# PP2_ptB.net
KiCad netlist of a schematic drawn in Altium Designer
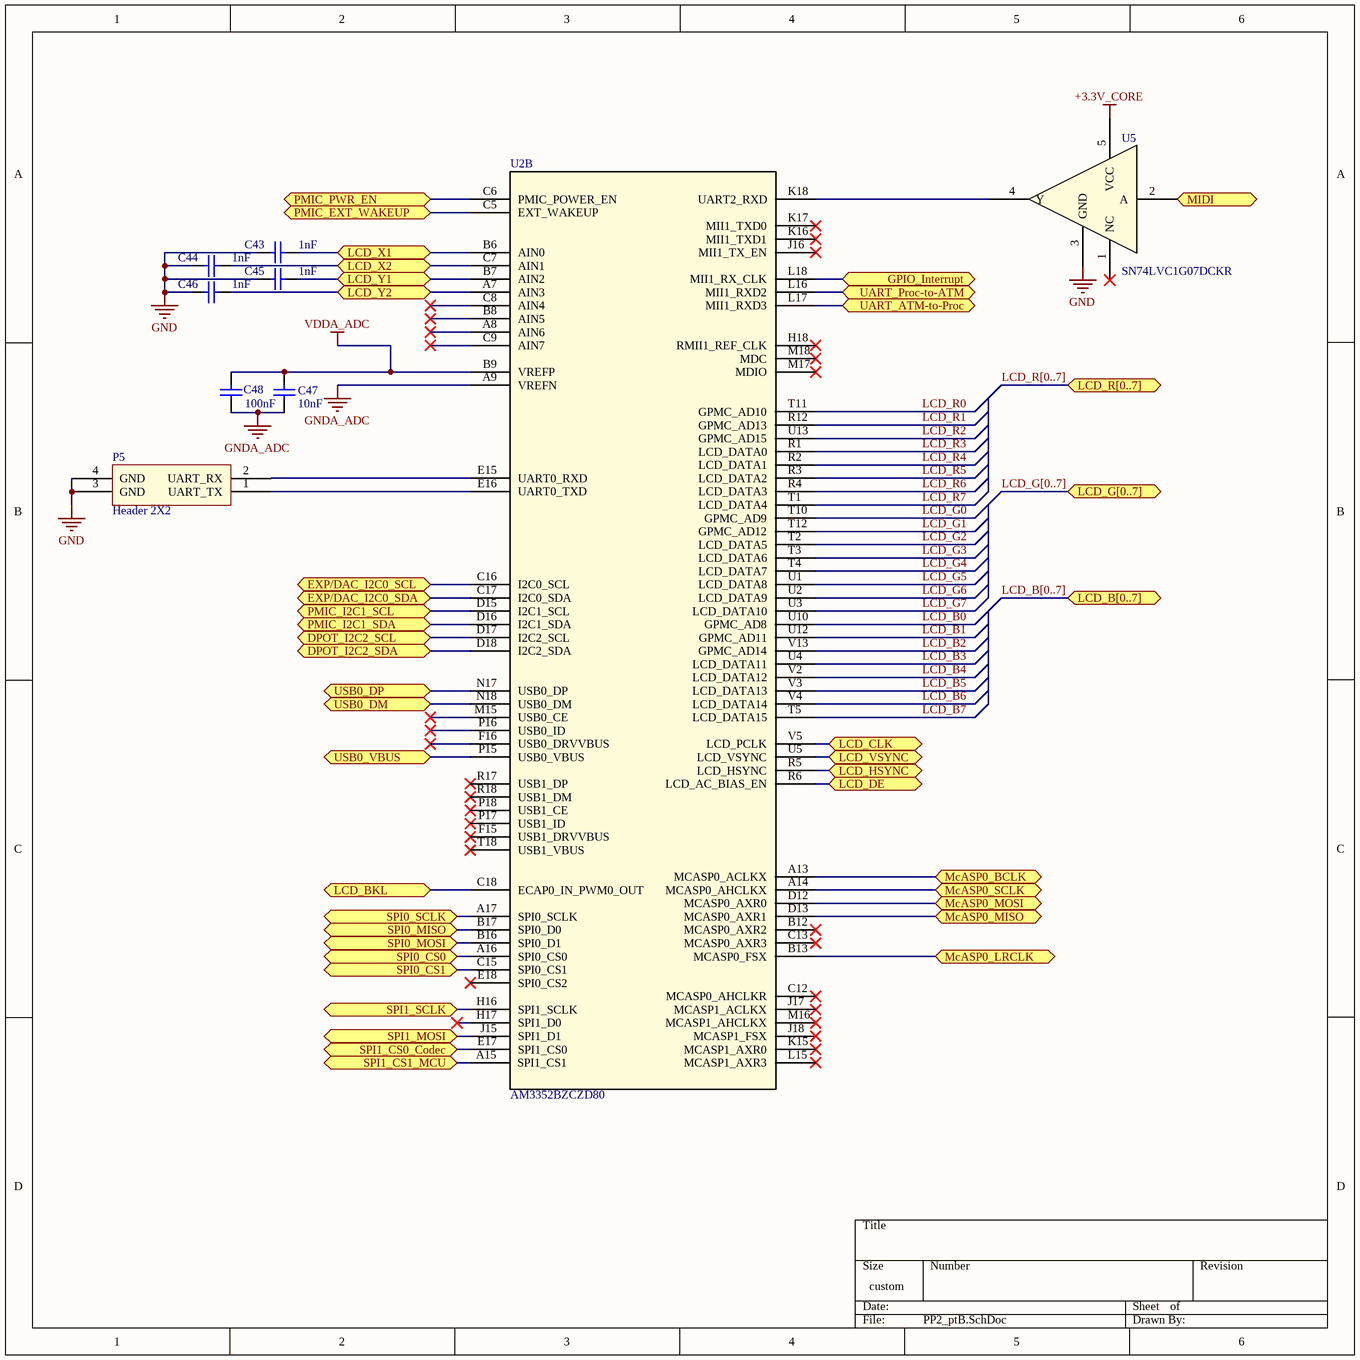
[diagram p0: PP2_ptB.SchDoc]

(export (version "E")
  (design (tool "Eeschema 10.0.6"))
  (components
    (comp (ref "C43")
      (value "1nF")
      (footprint "CAPC1608X08")
      (description "Capacitor")
      (fields (field (name "Comment") "Cap 1nF"))
      (libsource (lib "Michel") (part "Cap"))
    )
    (comp (ref "C44")
      (value "1nF")
      (footprint "CAPC1608X08")
      (description "Capacitor")
      (fields (field (name "Comment") "Cap 1nF"))
      (libsource (lib "Michel") (part "Cap"))
    )
    (comp (ref "C45")
      (value "1nF")
      (footprint "CAPC1608X08")
      (description "Capacitor")
      (fields (field (name "Comment") "Cap 1nF"))
      (libsource (lib "Michel") (part "Cap"))
    )
    (comp (ref "C46")
      (value "1nF")
      (footprint "CAPC1608X08")
      (description "Capacitor")
      (fields (field (name "Comment") "Cap 1nF"))
      (libsource (lib "Michel") (part "Cap"))
    )
    (comp (ref "C47")
      (value "10nF")
      (footprint "CAPC1005X05 (0402)")
      (description "Capacitor")
      (fields (field (name "Comment") "Cap 10uF"))
      (libsource (lib "Michel") (part "Cap"))
    )
    (comp (ref "C48")
      (value "100nF")
      (footprint "CAPC1005X05 (0402)")
      (description "Capacitor")
      (fields (field (name "Comment") "Cap 100nF"))
      (libsource (lib "Michel") (part "Cap"))
    )
    (comp (ref "P5")
      (value "Header 2X2")
      (footprint "CONN_1241050-2_T")
      (description "Header, 2-Pin, Dual row")
      (libsource (lib "Michel") (part "UART"))
    )
    (comp (ref "U2")
      (value "AM3352BZCZD80")
      (footprint "ZCZ324")
      (description "Microprocesseur ARM")
      (libsource (lib "Michel") (part "AM3352BZCZD80"))
    )
    (comp (ref "U5")
      (value "SN74LVC1G07DCKR")
      (footprint "DCK5")
      (description "Buffers & Transmetteurs")
      (libsource (lib "Michel") (part "SN74LVC1G07DCKR"))
    )
  )
  (nets
    (net (code "1") (name "+3.3V_CORE") (class "Default")
      (node (ref "U5") (pin "5") (pinfunction "VCC_5") (pintype "power_in"))
    )
    (net (code "2") (name "/DPOT_I2C2_SCL") (class "Default")
      (node (ref "U2") (pin "D17") (pinfunction "I2C2_SCL_D17") (pintype "passive"))
    )
    (net (code "3") (name "/DPOT_I2C2_SDA") (class "Default")
      (node (ref "U2") (pin "D18") (pinfunction "I2C2_SDA_D18") (pintype "passive"))
    )
    (net (code "4") (name "/EXP{slash}DAC_I2C0_SCL") (class "Default")
      (node (ref "U2") (pin "C16") (pinfunction "I2C0_SCL_C16") (pintype "passive"))
    )
    (net (code "5") (name "/EXP{slash}DAC_I2C0_SDA") (class "Default")
      (node (ref "U2") (pin "C17") (pinfunction "I2C0_SDA_C17") (pintype "passive"))
    )
    (net (code "6") (name "/GPIO_Interrupt") (class "Default")
      (node (ref "U2") (pin "L18") (pinfunction "MII1_RX_CLK_L18") (pintype "passive"))
    )
    (net (code "7") (name "/LCD_B0") (class "Default")
      (node (ref "U2") (pin "U10") (pinfunction "GPMC_AD8_U10") (pintype "passive"))
    )
    (net (code "8") (name "/LCD_B1") (class "Default")
      (node (ref "U2") (pin "U12") (pinfunction "GPMC_AD11_U12") (pintype "passive"))
    )
    (net (code "9") (name "/LCD_B2") (class "Default")
      (node (ref "U2") (pin "V13") (pinfunction "GPMC_AD14_V13") (pintype "passive"))
    )
    (net (code "10") (name "/LCD_B3") (class "Default")
      (node (ref "U2") (pin "U4") (pinfunction "LCD_DATA11_U4") (pintype "passive"))
    )
    (net (code "11") (name "/LCD_B4") (class "Default")
      (node (ref "U2") (pin "V2") (pinfunction "LCD_DATA12_V2") (pintype "passive"))
    )
    (net (code "12") (name "/LCD_B5") (class "Default")
      (node (ref "U2") (pin "V3") (pinfunction "LCD_DATA13_V3") (pintype "passive"))
    )
    (net (code "13") (name "/LCD_B6") (class "Default")
      (node (ref "U2") (pin "V4") (pinfunction "LCD_DATA14_V4") (pintype "passive"))
    )
    (net (code "14") (name "/LCD_B7") (class "Default")
      (node (ref "U2") (pin "T5") (pinfunction "LCD_DATA15_T5") (pintype "passive"))
    )
    (net (code "15") (name "/LCD_BKL") (class "Default")
      (node (ref "U2") (pin "C18") (pinfunction "ECAP0_IN_PWM0_OUT_C18") (pintype "passive"))
    )
    (net (code "17") (name "/LCD_CLK") (class "Default")
      (node (ref "U2") (pin "V5") (pinfunction "LCD_PCLK_V5") (pintype "passive"))
    )
    (net (code "18") (name "/LCD_DE") (class "Default")
      (node (ref "U2") (pin "R6") (pinfunction "LCD_AC_BIAS_EN_R6") (pintype "passive"))
    )
    (net (code "19") (name "/LCD_G0") (class "Default")
      (node (ref "U2") (pin "T10") (pinfunction "GPMC_AD9_T10") (pintype "passive"))
    )
    (net (code "20") (name "/LCD_G1") (class "Default")
      (node (ref "U2") (pin "T12") (pinfunction "GPMC_AD12_T12") (pintype "passive"))
    )
    (net (code "21") (name "/LCD_G2") (class "Default")
      (node (ref "U2") (pin "T2") (pinfunction "LCD_DATA5_T2") (pintype "passive"))
    )
    (net (code "22") (name "/LCD_G3") (class "Default")
      (node (ref "U2") (pin "T3") (pinfunction "LCD_DATA6_T3") (pintype "passive"))
    )
    (net (code "23") (name "/LCD_G4") (class "Default")
      (node (ref "U2") (pin "T4") (pinfunction "LCD_DATA7_T4") (pintype "passive"))
    )
    (net (code "24") (name "/LCD_G5") (class "Default")
      (node (ref "U2") (pin "U1") (pinfunction "LCD_DATA8_U1") (pintype "passive"))
    )
    (net (code "25") (name "/LCD_G6") (class "Default")
      (node (ref "U2") (pin "U2") (pinfunction "LCD_DATA9_U2") (pintype "passive"))
    )
    (net (code "26") (name "/LCD_G7") (class "Default")
      (node (ref "U2") (pin "U3") (pinfunction "LCD_DATA10_U3") (pintype "passive"))
    )
    (net (code "28") (name "/LCD_HSYNC") (class "Default")
      (node (ref "U2") (pin "R5") (pinfunction "LCD_HSYNC_R5") (pintype "passive"))
    )
    (net (code "29") (name "/LCD_R0") (class "Default")
      (node (ref "U2") (pin "T11") (pinfunction "GPMC_AD10_T11") (pintype "passive"))
    )
    (net (code "30") (name "/LCD_R1") (class "Default")
      (node (ref "U2") (pin "R12") (pinfunction "GPMC_AD13_R12") (pintype "passive"))
    )
    (net (code "31") (name "/LCD_R2") (class "Default")
      (node (ref "U2") (pin "U13") (pinfunction "GPMC_AD15_U13") (pintype "passive"))
    )
    (net (code "32") (name "/LCD_R3") (class "Default")
      (node (ref "U2") (pin "R1") (pinfunction "LCD_DATA0_R1") (pintype "passive"))
    )
    (net (code "33") (name "/LCD_R4") (class "Default")
      (node (ref "U2") (pin "R2") (pinfunction "LCD_DATA1_R2") (pintype "passive"))
    )
    (net (code "34") (name "/LCD_R5") (class "Default")
      (node (ref "U2") (pin "R3") (pinfunction "LCD_DATA2_R3") (pintype "passive"))
    )
    (net (code "35") (name "/LCD_R6") (class "Default")
      (node (ref "U2") (pin "R4") (pinfunction "LCD_DATA3_R4") (pintype "passive"))
    )
    (net (code "36") (name "/LCD_R7") (class "Default")
      (node (ref "U2") (pin "T1") (pinfunction "LCD_DATA4_T1") (pintype "passive"))
    )
    (net (code "38") (name "/LCD_VSYNC") (class "Default")
      (node (ref "U2") (pin "U5") (pinfunction "LCD_VSYNC_U5") (pintype "passive"))
    )
    (net (code "39") (name "/LCD_X1") (class "Default")
      (node (ref "C43") (pin "2") (pinfunction "2_2") (pintype "passive"))
      (node (ref "U2") (pin "B6") (pinfunction "AIN0_B6") (pintype "passive"))
    )
    (net (code "40") (name "/LCD_X2") (class "Default")
      (node (ref "C44") (pin "2") (pinfunction "2_2") (pintype "passive"))
      (node (ref "U2") (pin "C7") (pinfunction "AIN1_C7") (pintype "passive"))
    )
    (net (code "41") (name "/LCD_Y1") (class "Default")
      (node (ref "C45") (pin "2") (pinfunction "2_2") (pintype "passive"))
      (node (ref "U2") (pin "B7") (pinfunction "AIN2_B7") (pintype "passive"))
    )
    (net (code "42") (name "/LCD_Y2") (class "Default")
      (node (ref "C46") (pin "2") (pinfunction "2_2") (pintype "passive"))
      (node (ref "U2") (pin "A7") (pinfunction "AIN3_A7") (pintype "passive"))
    )
    (net (code "43") (name "/MIDI") (class "Default")
      (node (ref "U5") (pin "2") (pinfunction "A_2") (pintype "passive"))
    )
    (net (code "44") (name "/McASP0_BCLK") (class "Default")
      (node (ref "U2") (pin "A13") (pinfunction "MCASP0_ACLKX_A13") (pintype "passive"))
    )
    (net (code "45") (name "/McASP0_LRCLK") (class "Default")
      (node (ref "U2") (pin "B13") (pinfunction "MCASP0_FSX_B13") (pintype "passive"))
    )
    (net (code "46") (name "/McASP0_MISO") (class "Default")
      (node (ref "U2") (pin "D13") (pinfunction "MCASP0_AXR1_D13") (pintype "passive"))
    )
    (net (code "47") (name "/McASP0_MOSI") (class "Default")
      (node (ref "U2") (pin "D12") (pinfunction "MCASP0_AXR0_D12") (pintype "passive"))
    )
    (net (code "48") (name "/McASP0_SCLK") (class "Default")
      (node (ref "U2") (pin "A14") (pinfunction "MCASP0_AHCLKX_A14") (pintype "passive"))
    )
    (net (code "49") (name "/PMIC_EXT_WAKEUP") (class "Default")
      (node (ref "U2") (pin "C5") (pinfunction "EXT_WAKEUP_C5") (pintype "passive"))
    )
    (net (code "50") (name "/PMIC_I2C1_SCL") (class "Default")
      (node (ref "U2") (pin "D15") (pinfunction "I2C1_SCL_D15") (pintype "passive"))
    )
    (net (code "51") (name "/PMIC_I2C1_SDA") (class "Default")
      (node (ref "U2") (pin "D16") (pinfunction "I2C1_SDA_D16") (pintype "passive"))
    )
    (net (code "52") (name "/PMIC_PWR_EN") (class "Default")
      (node (ref "U2") (pin "C6") (pinfunction "PMIC_POWER_EN_C6") (pintype "passive"))
    )
    (net (code "53") (name "/SPI0_CS0") (class "Default")
      (node (ref "U2") (pin "A16") (pinfunction "SPI0_CS0_A16") (pintype "passive"))
    )
    (net (code "54") (name "/SPI0_CS1") (class "Default")
      (node (ref "U2") (pin "C15") (pinfunction "SPI0_CS1_C15") (pintype "passive"))
    )
    (net (code "55") (name "/SPI0_MISO") (class "Default")
      (node (ref "U2") (pin "B17") (pinfunction "SPI0_D0_B17") (pintype "passive"))
    )
    (net (code "56") (name "/SPI0_MOSI") (class "Default")
      (node (ref "U2") (pin "B16") (pinfunction "SPI0_D1_B16") (pintype "passive"))
    )
    (net (code "57") (name "/SPI0_SCLK") (class "Default")
      (node (ref "U2") (pin "A17") (pinfunction "SPI0_SCLK_A17") (pintype "passive"))
    )
    (net (code "58") (name "/SPI1_CS0_Codec") (class "Default")
      (node (ref "U2") (pin "E17") (pinfunction "SPI1_CS0_E17") (pintype "passive"))
    )
    (net (code "59") (name "/SPI1_CS1_MCU") (class "Default")
      (node (ref "U2") (pin "A15") (pinfunction "SPI1_CS1_A15") (pintype "passive"))
    )
    (net (code "60") (name "/SPI1_MOSI") (class "Default")
      (node (ref "U2") (pin "J15") (pinfunction "SPI1_D1_J15") (pintype "passive"))
    )
    (net (code "61") (name "/SPI1_SCLK") (class "Default")
      (node (ref "U2") (pin "H16") (pinfunction "SPI1_SCLK_H16") (pintype "passive"))
    )
    (net (code "62") (name "/UART_ATM-to-Proc") (class "Default")
      (node (ref "U2") (pin "L17") (pinfunction "MII1_RXD3_L17") (pintype "passive"))
    )
    (net (code "63") (name "/UART_Proc-to-ATM") (class "Default")
      (node (ref "U2") (pin "L16") (pinfunction "MII1_RXD2_L16") (pintype "passive"))
    )
    (net (code "64") (name "/USB0_DM") (class "Default")
      (node (ref "U2") (pin "N18") (pinfunction "USB0_DM_N18") (pintype "passive"))
    )
    (net (code "65") (name "/USB0_DP") (class "Default")
      (node (ref "U2") (pin "N17") (pinfunction "USB0_DP_N17") (pintype "passive"))
    )
    (net (code "66") (name "/USB0_VBUS") (class "Default")
      (node (ref "U2") (pin "P15") (pinfunction "USB0_VBUS_P15") (pintype "passive"))
    )
    (net (code "67") (name "GND") (class "Default")
      (node (ref "C43") (pin "1") (pinfunction "1_1") (pintype "passive"))
      (node (ref "C44") (pin "1") (pinfunction "1_1") (pintype "passive"))
      (node (ref "C45") (pin "1") (pinfunction "1_1") (pintype "passive"))
      (node (ref "C46") (pin "1") (pinfunction "1_1") (pintype "passive"))
      (node (ref "P5") (pin "3") (pinfunction "GND_3") (pintype "passive"))
      (node (ref "P5") (pin "4") (pinfunction "GND_4") (pintype "passive"))
      (node (ref "U5") (pin "3") (pinfunction "GND_3") (pintype "power_in"))
    )
    (net (code "68") (name "GNDA_ADC") (class "Default")
      (node (ref "C47") (pin "2") (pinfunction "2_2") (pintype "passive"))
      (node (ref "C48") (pin "2") (pinfunction "2_2") (pintype "passive"))
      (node (ref "U2") (pin "A9") (pinfunction "VREFN_A9") (pintype "passive"))
    )
    (net (code "69") (name "Net-(P5-UART_RX)") (class "Default")
      (node (ref "P5") (pin "2") (pinfunction "UART_RX_2") (pintype "passive"))
      (node (ref "U2") (pin "E15") (pinfunction "UART0_RXD_E15") (pintype "passive"))
    )
    (net (code "70") (name "Net-(P5-UART_TX)") (class "Default")
      (node (ref "P5") (pin "1") (pinfunction "UART_TX_1") (pintype "passive"))
      (node (ref "U2") (pin "E16") (pinfunction "UART0_TXD_E16") (pintype "passive"))
    )
    (net (code "71") (name "Net-(U2B-UART2_RXD)") (class "Default")
      (node (ref "U2") (pin "K18") (pinfunction "UART2_RXD_K18") (pintype "passive"))
      (node (ref "U5") (pin "4") (pinfunction "Y_4") (pintype "passive"))
    )
    (net (code "72") (name "VDDA_ADC") (class "Default")
      (node (ref "C47") (pin "1") (pinfunction "1_1") (pintype "passive"))
      (node (ref "C48") (pin "1") (pinfunction "1_1") (pintype "passive"))
      (node (ref "U2") (pin "B9") (pinfunction "VREFP_B9") (pintype "passive"))
    )
    (net (code "73") (name "unconnected-(U2B-AIN4-PadC8)") (class "Default")
      (node (ref "U2") (pin "C8") (pinfunction "AIN4_C8") (pintype "passive+no_connect"))
    )
    (net (code "74") (name "unconnected-(U2B-AIN5-PadB8)") (class "Default")
      (node (ref "U2") (pin "B8") (pinfunction "AIN5_B8") (pintype "passive+no_connect"))
    )
    (net (code "75") (name "unconnected-(U2B-AIN6-PadA8)") (class "Default")
      (node (ref "U2") (pin "A8") (pinfunction "AIN6_A8") (pintype "passive+no_connect"))
    )
    (net (code "76") (name "unconnected-(U2B-AIN7-PadC9)") (class "Default")
      (node (ref "U2") (pin "C9") (pinfunction "AIN7_C9") (pintype "passive+no_connect"))
    )
    (net (code "77") (name "unconnected-(U2B-MCASP0_AHCLKR-PadC12)") (class "Default")
      (node (ref "U2") (pin "C12") (pinfunction "MCASP0_AHCLKR_C12") (pintype "passive+no_connect"))
    )
    (net (code "78") (name "unconnected-(U2B-MCASP0_AXR2-PadB12)") (class "Default")
      (node (ref "U2") (pin "B12") (pinfunction "MCASP0_AXR2_B12") (pintype "passive+no_connect"))
    )
    (net (code "79") (name "unconnected-(U2B-MCASP0_AXR3-PadC13)") (class "Default")
      (node (ref "U2") (pin "C13") (pinfunction "MCASP0_AXR3_C13") (pintype "passive+no_connect"))
    )
    (net (code "80") (name "unconnected-(U2B-MCASP1_ACLKX-PadJ17)") (class "Default")
      (node (ref "U2") (pin "J17") (pinfunction "MCASP1_ACLKX_J17") (pintype "passive+no_connect"))
    )
    (net (code "81") (name "unconnected-(U2B-MCASP1_AHCLKX-PadM16)") (class "Default")
      (node (ref "U2") (pin "M16") (pinfunction "MCASP1_AHCLKX_M16") (pintype "passive+no_connect"))
    )
    (net (code "82") (name "unconnected-(U2B-MCASP1_AXR0-PadK15)") (class "Default")
      (node (ref "U2") (pin "K15") (pinfunction "MCASP1_AXR0_K15") (pintype "passive+no_connect"))
    )
    (net (code "83") (name "unconnected-(U2B-MCASP1_AXR3-PadL15)") (class "Default")
      (node (ref "U2") (pin "L15") (pinfunction "MCASP1_AXR3_L15") (pintype "passive+no_connect"))
    )
    (net (code "84") (name "unconnected-(U2B-MCASP1_FSX-PadJ18)") (class "Default")
      (node (ref "U2") (pin "J18") (pinfunction "MCASP1_FSX_J18") (pintype "passive+no_connect"))
    )
    (net (code "85") (name "unconnected-(U2B-MDC-PadM18)") (class "Default")
      (node (ref "U2") (pin "M18") (pinfunction "MDC_M18") (pintype "passive+no_connect"))
    )
    (net (code "86") (name "unconnected-(U2B-MDIO-PadM17)") (class "Default")
      (node (ref "U2") (pin "M17") (pinfunction "MDIO_M17") (pintype "passive+no_connect"))
    )
    (net (code "87") (name "unconnected-(U2B-MII1_TXD0-PadK17)") (class "Default")
      (node (ref "U2") (pin "K17") (pinfunction "MII1_TXD0_K17") (pintype "passive+no_connect"))
    )
    (net (code "88") (name "unconnected-(U2B-MII1_TXD1-PadK16)") (class "Default")
      (node (ref "U2") (pin "K16") (pinfunction "MII1_TXD1_K16") (pintype "passive+no_connect"))
    )
    (net (code "89") (name "unconnected-(U2B-MII1_TX_EN-PadJ16)") (class "Default")
      (node (ref "U2") (pin "J16") (pinfunction "MII1_TX_EN_J16") (pintype "passive+no_connect"))
    )
    (net (code "90") (name "unconnected-(U2B-RMII1_REF_CLK-PadH18)") (class "Default")
      (node (ref "U2") (pin "H18") (pinfunction "RMII1_REF_CLK_H18") (pintype "passive+no_connect"))
    )
    (net (code "91") (name "unconnected-(U2B-SPI0_CS2-PadE18)") (class "Default")
      (node (ref "U2") (pin "E18") (pinfunction "SPI0_CS2_E18") (pintype "passive+no_connect"))
    )
    (net (code "92") (name "unconnected-(U2B-SPI1_D0-PadH17)") (class "Default")
      (node (ref "U2") (pin "H17") (pinfunction "SPI1_D0_H17") (pintype "passive+no_connect"))
    )
    (net (code "93") (name "unconnected-(U2B-USB0_CE-PadM15)") (class "Default")
      (node (ref "U2") (pin "M15") (pinfunction "USB0_CE_M15") (pintype "passive+no_connect"))
    )
    (net (code "94") (name "unconnected-(U2B-USB0_DRVVBUS-PadF16)") (class "Default")
      (node (ref "U2") (pin "F16") (pinfunction "USB0_DRVVBUS_F16") (pintype "passive+no_connect"))
    )
    (net (code "95") (name "unconnected-(U2B-USB0_ID-PadP16)") (class "Default")
      (node (ref "U2") (pin "P16") (pinfunction "USB0_ID_P16") (pintype "passive+no_connect"))
    )
    (net (code "96") (name "unconnected-(U2B-USB1_CE-PadP18)") (class "Default")
      (node (ref "U2") (pin "P18") (pinfunction "USB1_CE_P18") (pintype "passive+no_connect"))
    )
    (net (code "97") (name "unconnected-(U2B-USB1_DM-PadR18)") (class "Default")
      (node (ref "U2") (pin "R18") (pinfunction "USB1_DM_R18") (pintype "passive+no_connect"))
    )
    (net (code "98") (name "unconnected-(U2B-USB1_DP-PadR17)") (class "Default")
      (node (ref "U2") (pin "R17") (pinfunction "USB1_DP_R17") (pintype "passive+no_connect"))
    )
    (net (code "99") (name "unconnected-(U2B-USB1_DRVVBUS-PadF15)") (class "Default")
      (node (ref "U2") (pin "F15") (pinfunction "USB1_DRVVBUS_F15") (pintype "passive+no_connect"))
    )
    (net (code "100") (name "unconnected-(U2B-USB1_ID-PadP17)") (class "Default")
      (node (ref "U2") (pin "P17") (pinfunction "USB1_ID_P17") (pintype "passive+no_connect"))
    )
    (net (code "101") (name "unconnected-(U2B-USB1_VBUS-PadT18)") (class "Default")
      (node (ref "U2") (pin "T18") (pinfunction "USB1_VBUS_T18") (pintype "passive+no_connect"))
    )
    (net (code "102") (name "unconnected-(U5-NC-Pad1)") (class "Default")
      (node (ref "U5") (pin "1") (pinfunction "NC_1") (pintype "passive+no_connect"))
    )
  )
)
